# 09-I225-2.net
KiCad netlist of a schematic drawn in Altium Designer
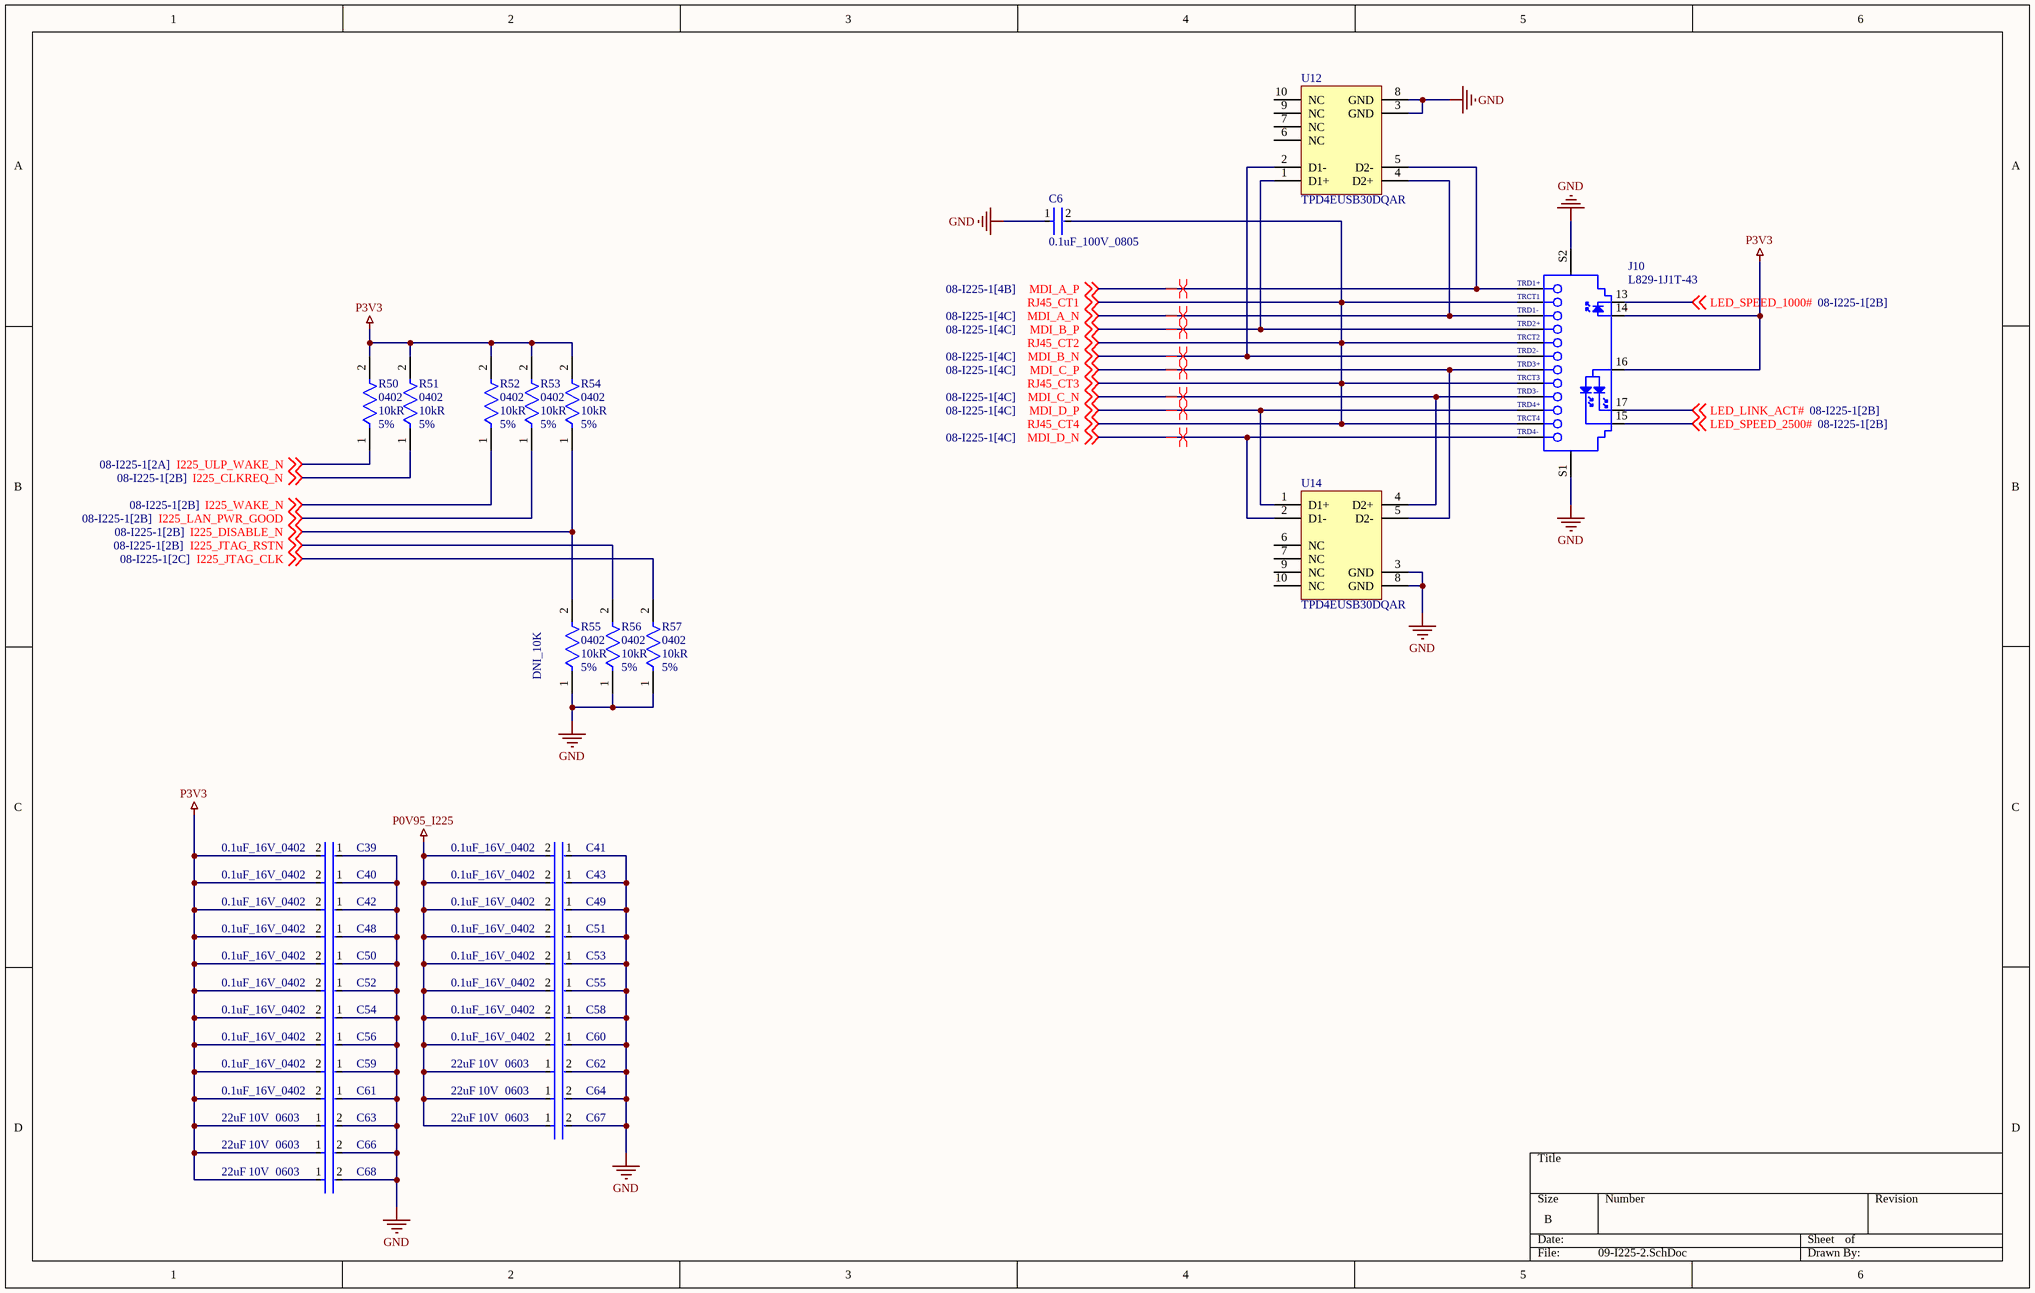
[diagram p0: 09-I225-2.SchDoc]

(export (version "E")
  (design (tool "Eeschema 10.0.6"))
  (components
    (comp (ref "C6")
      (value "0.1uF_100V_0805")
      (footprint "FP-0805-L_2_0_0_1-W_1_25-MFG")
      (description "Multilayer Ceramic Capacitor 0.1 uF 100V X7R 20% SMD 0805 T/R")
      (fields (field (name "TOLERANCE") "20%"))
      (libsource (lib "Altium Content Vault") (part "b4654b650e69147ec39a6b967a45e02"))
    )
    (comp (ref "C39")
      (value "0.1uF_16V_0402")
      (footprint "FP-GRM15-MFG")
      (description "CAP CER 0.1UF 16V X7R 0402")
      (fields (field (name "MANUFACTURER PART NUMBER") "GRM155R71C104KA88D") (field (name "TOLERANCE") "10%"))
      (libsource (lib "Altium Content Vault") (part "236180d848d6139a670b325ea6854c9"))
    )
    (comp (ref "C40")
      (value "0.1uF_16V_0402")
      (footprint "FP-GRM15-MFG")
      (description "CAP CER 0.1UF 16V X7R 0402")
      (fields (field (name "MANUFACTURER PART NUMBER") "GRM155R71C104KA88D") (field (name "TOLERANCE") "10%"))
      (libsource (lib "Altium Content Vault") (part "236180d848d6139a670b325ea6854c9"))
    )
    (comp (ref "C41")
      (value "0.1uF_16V_0402")
      (footprint "FP-GRM15-MFG")
      (description "CAP CER 0.1UF 16V X7R 0402")
      (fields (field (name "MANUFACTURER PART NUMBER") "GRM155R71C104KA88D") (field (name "TOLERANCE") "10%"))
      (libsource (lib "Altium Content Vault") (part "236180d848d6139a670b325ea6854c9"))
    )
    (comp (ref "C42")
      (value "0.1uF_16V_0402")
      (footprint "FP-GRM15-MFG")
      (description "CAP CER 0.1UF 16V X7R 0402")
      (fields (field (name "MANUFACTURER PART NUMBER") "GRM155R71C104KA88D") (field (name "TOLERANCE") "10%"))
      (libsource (lib "Altium Content Vault") (part "236180d848d6139a670b325ea6854c9"))
    )
    (comp (ref "C43")
      (value "0.1uF_16V_0402")
      (footprint "FP-GRM15-MFG")
      (description "CAP CER 0.1UF 16V X7R 0402")
      (fields (field (name "MANUFACTURER PART NUMBER") "GRM155R71C104KA88D") (field (name "TOLERANCE") "10%"))
      (libsource (lib "Altium Content Vault") (part "236180d848d6139a670b325ea6854c9"))
    )
    (comp (ref "C48")
      (value "0.1uF_16V_0402")
      (footprint "FP-GRM15-MFG")
      (description "CAP CER 0.1UF 16V X7R 0402")
      (fields (field (name "MANUFACTURER PART NUMBER") "GRM155R71C104KA88D") (field (name "TOLERANCE") "10%"))
      (libsource (lib "Altium Content Vault") (part "236180d848d6139a670b325ea6854c9"))
    )
    (comp (ref "C49")
      (value "0.1uF_16V_0402")
      (footprint "FP-GRM15-MFG")
      (description "CAP CER 0.1UF 16V X7R 0402")
      (fields (field (name "MANUFACTURER PART NUMBER") "GRM155R71C104KA88D") (field (name "TOLERANCE") "10%"))
      (libsource (lib "Altium Content Vault") (part "236180d848d6139a670b325ea6854c9"))
    )
    (comp (ref "C50")
      (value "0.1uF_16V_0402")
      (footprint "FP-GRM15-MFG")
      (description "CAP CER 0.1UF 16V X7R 0402")
      (fields (field (name "MANUFACTURER PART NUMBER") "GRM155R71C104KA88D") (field (name "TOLERANCE") "10%"))
      (libsource (lib "Altium Content Vault") (part "236180d848d6139a670b325ea6854c9"))
    )
    (comp (ref "C51")
      (value "0.1uF_16V_0402")
      (footprint "FP-GRM15-MFG")
      (description "CAP CER 0.1UF 16V X7R 0402")
      (fields (field (name "MANUFACTURER PART NUMBER") "GRM155R71C104KA88D") (field (name "TOLERANCE") "10%"))
      (libsource (lib "Altium Content Vault") (part "236180d848d6139a670b325ea6854c9"))
    )
    (comp (ref "C52")
      (value "0.1uF_16V_0402")
      (footprint "FP-GRM15-MFG")
      (description "CAP CER 0.1UF 16V X7R 0402")
      (fields (field (name "MANUFACTURER PART NUMBER") "GRM155R71C104KA88D") (field (name "TOLERANCE") "10%"))
      (libsource (lib "Altium Content Vault") (part "236180d848d6139a670b325ea6854c9"))
    )
    (comp (ref "C53")
      (value "0.1uF_16V_0402")
      (footprint "FP-GRM15-MFG")
      (description "CAP CER 0.1UF 16V X7R 0402")
      (fields (field (name "MANUFACTURER PART NUMBER") "GRM155R71C104KA88D") (field (name "TOLERANCE") "10%"))
      (libsource (lib "Altium Content Vault") (part "236180d848d6139a670b325ea6854c9"))
    )
    (comp (ref "C54")
      (value "0.1uF_16V_0402")
      (footprint "FP-GRM15-MFG")
      (description "CAP CER 0.1UF 16V X7R 0402")
      (fields (field (name "MANUFACTURER PART NUMBER") "GRM155R71C104KA88D") (field (name "TOLERANCE") "10%"))
      (libsource (lib "Altium Content Vault") (part "236180d848d6139a670b325ea6854c9"))
    )
    (comp (ref "C55")
      (value "0.1uF_16V_0402")
      (footprint "FP-GRM15-MFG")
      (description "CAP CER 0.1UF 16V X7R 0402")
      (fields (field (name "MANUFACTURER PART NUMBER") "GRM155R71C104KA88D") (field (name "TOLERANCE") "10%"))
      (libsource (lib "Altium Content Vault") (part "236180d848d6139a670b325ea6854c9"))
    )
    (comp (ref "C56")
      (value "0.1uF_16V_0402")
      (footprint "FP-GRM15-MFG")
      (description "CAP CER 0.1UF 16V X7R 0402")
      (fields (field (name "MANUFACTURER PART NUMBER") "GRM155R71C104KA88D") (field (name "TOLERANCE") "10%"))
      (libsource (lib "Altium Content Vault") (part "236180d848d6139a670b325ea6854c9"))
    )
    (comp (ref "C58")
      (value "0.1uF_16V_0402")
      (footprint "FP-GRM15-MFG")
      (description "CAP CER 0.1UF 16V X7R 0402")
      (fields (field (name "MANUFACTURER PART NUMBER") "GRM155R71C104KA88D") (field (name "TOLERANCE") "10%"))
      (libsource (lib "Altium Content Vault") (part "236180d848d6139a670b325ea6854c9"))
    )
    (comp (ref "C59")
      (value "0.1uF_16V_0402")
      (footprint "FP-GRM15-MFG")
      (description "CAP CER 0.1UF 16V X7R 0402")
      (fields (field (name "MANUFACTURER PART NUMBER") "GRM155R71C104KA88D") (field (name "TOLERANCE") "10%"))
      (libsource (lib "Altium Content Vault") (part "236180d848d6139a670b325ea6854c9"))
    )
    (comp (ref "C60")
      (value "0.1uF_16V_0402")
      (footprint "FP-GRM15-MFG")
      (description "CAP CER 0.1UF 16V X7R 0402")
      (fields (field (name "MANUFACTURER PART NUMBER") "GRM155R71C104KA88D") (field (name "TOLERANCE") "10%"))
      (libsource (lib "Altium Content Vault") (part "236180d848d6139a670b325ea6854c9"))
    )
    (comp (ref "C61")
      (value "0.1uF_16V_0402")
      (footprint "FP-GRM15-MFG")
      (description "CAP CER 0.1UF 16V X7R 0402")
      (fields (field (name "MANUFACTURER PART NUMBER") "GRM155R71C104KA88D") (field (name "TOLERANCE") "10%"))
      (libsource (lib "Altium Content Vault") (part "236180d848d6139a670b325ea6854c9"))
    )
    (comp (ref "C62")
      (value "GRM188R61A226ME15D")
      (footprint "FP-GRM188-0_2-IPC_C")
      (description "Chip Multilayer Ceramic Capacitors for General Purpose, 0603, 22uF, X5R, 15%, 20%, 10V")
      (fields
        (field (name "TOLERANCE") "20%")
        (field (name "CAPACITANCE") "22uF")
        (field (name "VOLTAGE RATING") "10V")
        (field (name "CASE CODE (IMPERIAL)") "0603")
      )
      (libsource (lib "Altium Content Vault") (part "11868f565c42a9108669ba33697ecf6"))
    )
    (comp (ref "C63")
      (value "GRM188R61A226ME15D")
      (footprint "FP-GRM188-0_2-IPC_C")
      (description "Chip Multilayer Ceramic Capacitors for General Purpose, 0603, 22uF, X5R, 15%, 20%, 10V")
      (fields
        (field (name "TOLERANCE") "20%")
        (field (name "CAPACITANCE") "22uF")
        (field (name "VOLTAGE RATING") "10V")
        (field (name "CASE CODE (IMPERIAL)") "0603")
      )
      (libsource (lib "Altium Content Vault") (part "11868f565c42a9108669ba33697ecf6"))
    )
    (comp (ref "C64")
      (value "GRM188R61A226ME15D")
      (footprint "FP-GRM188-0_2-IPC_C")
      (description "Chip Multilayer Ceramic Capacitors for General Purpose, 0603, 22uF, X5R, 15%, 20%, 10V")
      (fields
        (field (name "TOLERANCE") "20%")
        (field (name "CAPACITANCE") "22uF")
        (field (name "VOLTAGE RATING") "10V")
        (field (name "CASE CODE (IMPERIAL)") "0603")
      )
      (libsource (lib "Altium Content Vault") (part "11868f565c42a9108669ba33697ecf6"))
    )
    (comp (ref "C66")
      (value "GRM188R61A226ME15D")
      (footprint "FP-GRM188-0_2-IPC_C")
      (description "Chip Multilayer Ceramic Capacitors for General Purpose, 0603, 22uF, X5R, 15%, 20%, 10V")
      (fields
        (field (name "TOLERANCE") "20%")
        (field (name "CAPACITANCE") "22uF")
        (field (name "VOLTAGE RATING") "10V")
        (field (name "CASE CODE (IMPERIAL)") "0603")
      )
      (libsource (lib "Altium Content Vault") (part "11868f565c42a9108669ba33697ecf6"))
    )
    (comp (ref "C67")
      (value "GRM188R61A226ME15D")
      (footprint "FP-GRM188-0_2-IPC_C")
      (description "Chip Multilayer Ceramic Capacitors for General Purpose, 0603, 22uF, X5R, 15%, 20%, 10V")
      (fields
        (field (name "TOLERANCE") "20%")
        (field (name "CAPACITANCE") "22uF")
        (field (name "VOLTAGE RATING") "10V")
        (field (name "CASE CODE (IMPERIAL)") "0603")
      )
      (libsource (lib "Altium Content Vault") (part "11868f565c42a9108669ba33697ecf6"))
    )
    (comp (ref "C68")
      (value "GRM188R61A226ME15D")
      (footprint "FP-GRM188-0_2-IPC_C")
      (description "Chip Multilayer Ceramic Capacitors for General Purpose, 0603, 22uF, X5R, 15%, 20%, 10V")
      (fields
        (field (name "TOLERANCE") "20%")
        (field (name "CAPACITANCE") "22uF")
        (field (name "VOLTAGE RATING") "10V")
        (field (name "CASE CODE (IMPERIAL)") "0603")
      )
      (libsource (lib "Altium Content Vault") (part "11868f565c42a9108669ba33697ecf6"))
    )
    (comp (ref "J10")
      (value "L829-1J1T-43")
      (footprint "BELS-L829-1J1T-43_V")
      (description "Gigabit MagJack(R) Ultra Low Profile, 10/100/1000 Base-T, 19-Pin THD, RoHS, Tray")
      (libsource (lib "Altium Content Vault") (part "RJ45-17-2SHLD"))
    )
    (comp (ref "R50")
      (value "CRCW040210K0JNED")
      (footprint "FP-CRCW0402-e3-IPC_B")
      (description "RES Thick Film, 10kΩ, 5%, 0.063W, 200ppm/°C, 0402")
      (fields
        (field (name "CASE/PACKAGE") "0402")
        (field (name "RESISTANCE") "10kR")
        (field (name "TOLERANCE") "5%")
      )
      (libsource (lib "Altium Content Vault") (part "1029c3af85768c4190bb7ad29bc67b5"))
    )
    (comp (ref "R51")
      (value "CRCW040210K0JNED")
      (footprint "FP-CRCW0402-e3-IPC_B")
      (description "RES Thick Film, 10kΩ, 5%, 0.063W, 200ppm/°C, 0402")
      (fields
        (field (name "CASE/PACKAGE") "0402")
        (field (name "RESISTANCE") "10kR")
        (field (name "TOLERANCE") "5%")
      )
      (libsource (lib "Altium Content Vault") (part "1029c3af85768c4190bb7ad29bc67b5"))
    )
    (comp (ref "R52")
      (value "CRCW040210K0JNED")
      (footprint "FP-CRCW0402-e3-IPC_B")
      (description "RES Thick Film, 10kΩ, 5%, 0.063W, 200ppm/°C, 0402")
      (fields
        (field (name "CASE/PACKAGE") "0402")
        (field (name "RESISTANCE") "10kR")
        (field (name "TOLERANCE") "5%")
      )
      (libsource (lib "Altium Content Vault") (part "1029c3af85768c4190bb7ad29bc67b5"))
    )
    (comp (ref "R53")
      (value "CRCW040210K0JNED")
      (footprint "FP-CRCW0402-e3-IPC_B")
      (description "RES Thick Film, 10kΩ, 5%, 0.063W, 200ppm/°C, 0402")
      (fields
        (field (name "CASE/PACKAGE") "0402")
        (field (name "RESISTANCE") "10kR")
        (field (name "TOLERANCE") "5%")
      )
      (libsource (lib "Altium Content Vault") (part "1029c3af85768c4190bb7ad29bc67b5"))
    )
    (comp (ref "R54")
      (value "CRCW040210K0JNED")
      (footprint "FP-CRCW0402-e3-IPC_B")
      (description "RES Thick Film, 10kΩ, 5%, 0.063W, 200ppm/°C, 0402")
      (fields
        (field (name "CASE/PACKAGE") "0402")
        (field (name "RESISTANCE") "10kR")
        (field (name "TOLERANCE") "5%")
      )
      (libsource (lib "Altium Content Vault") (part "1029c3af85768c4190bb7ad29bc67b5"))
    )
    (comp (ref "R55")
      (value "DNI_10K")
      (footprint "FP-CRCW0402-e3-IPC_B")
      (description "RES Thick Film, 10kΩ, 5%, 0.063W, 200ppm/°C, 0402")
      (fields
        (field (name "CASE/PACKAGE") "0402")
        (field (name "RESISTANCE") "10kR")
        (field (name "TOLERANCE") "5%")
      )
      (libsource (lib "Altium Content Vault") (part "1029c3af85768c4190bb7ad29bc67b5"))
    )
    (comp (ref "R56")
      (value "CRCW040210K0JNED")
      (footprint "FP-CRCW0402-e3-IPC_B")
      (description "RES Thick Film, 10kΩ, 5%, 0.063W, 200ppm/°C, 0402")
      (fields
        (field (name "CASE/PACKAGE") "0402")
        (field (name "RESISTANCE") "10kR")
        (field (name "TOLERANCE") "5%")
      )
      (libsource (lib "Altium Content Vault") (part "1029c3af85768c4190bb7ad29bc67b5"))
    )
    (comp (ref "R57")
      (value "CRCW040210K0JNED")
      (footprint "FP-CRCW0402-e3-IPC_B")
      (description "RES Thick Film, 10kΩ, 5%, 0.063W, 200ppm/°C, 0402")
      (fields
        (field (name "CASE/PACKAGE") "0402")
        (field (name "RESISTANCE") "10kR")
        (field (name "TOLERANCE") "5%")
      )
      (libsource (lib "Altium Content Vault") (part "1029c3af85768c4190bb7ad29bc67b5"))
    )
    (comp (ref "U12")
      (value "TPD4EUSB30DQAR")
      (footprint "DQA0010A_V")
      (fields (field (name "MANUFACTURER") "Texas Instruments"))
      (libsource (lib "Altium Content Vault") (part "TI-TPD4EUSB30-SON_DQA-10"))
    )
    (comp (ref "U14")
      (value "TPD4EUSB30DQAR")
      (footprint "DQA0010A_V")
      (fields (field (name "MANUFACTURER") "Texas Instruments"))
      (libsource (lib "") (part "TI-TPD4EUSB30-SON_DQA-10_1"))
    )
  )
  (nets
    (net (code "1") (name "GND") (class "Default")
      (node (ref "C39") (pin "1") (pinfunction "1_1") (pintype "passive"))
      (node (ref "C40") (pin "1") (pinfunction "1_1") (pintype "passive"))
      (node (ref "C41") (pin "1") (pinfunction "1_1") (pintype "passive"))
      (node (ref "C42") (pin "1") (pinfunction "1_1") (pintype "passive"))
      (node (ref "C43") (pin "1") (pinfunction "1_1") (pintype "passive"))
      (node (ref "C48") (pin "1") (pinfunction "1_1") (pintype "passive"))
      (node (ref "C49") (pin "1") (pinfunction "1_1") (pintype "passive"))
      (node (ref "C50") (pin "1") (pinfunction "1_1") (pintype "passive"))
      (node (ref "C51") (pin "1") (pinfunction "1_1") (pintype "passive"))
      (node (ref "C52") (pin "1") (pinfunction "1_1") (pintype "passive"))
      (node (ref "C53") (pin "1") (pinfunction "1_1") (pintype "passive"))
      (node (ref "C54") (pin "1") (pinfunction "1_1") (pintype "passive"))
      (node (ref "C55") (pin "1") (pinfunction "1_1") (pintype "passive"))
      (node (ref "C56") (pin "1") (pinfunction "1_1") (pintype "passive"))
      (node (ref "C58") (pin "1") (pinfunction "1_1") (pintype "passive"))
      (node (ref "C59") (pin "1") (pinfunction "1_1") (pintype "passive"))
      (node (ref "C6") (pin "1") (pinfunction "1_1") (pintype "passive"))
      (node (ref "C60") (pin "1") (pinfunction "1_1") (pintype "passive"))
      (node (ref "C61") (pin "1") (pinfunction "1_1") (pintype "passive"))
      (node (ref "C62") (pin "2") (pinfunction "2_2") (pintype "passive"))
      (node (ref "C63") (pin "2") (pinfunction "2_2") (pintype "passive"))
      (node (ref "C64") (pin "2") (pinfunction "2_2") (pintype "passive"))
      (node (ref "C66") (pin "2") (pinfunction "2_2") (pintype "passive"))
      (node (ref "C67") (pin "2") (pinfunction "2_2") (pintype "passive"))
      (node (ref "C68") (pin "2") (pinfunction "2_2") (pintype "passive"))
      (node (ref "J10") (pin "S1") (pinfunction "S1_S1") (pintype "passive"))
      (node (ref "J10") (pin "S2") (pinfunction "S2_S2") (pintype "passive"))
      (node (ref "R55") (pin "1") (pinfunction "1_1") (pintype "passive"))
      (node (ref "R56") (pin "1") (pinfunction "1_1") (pintype "passive"))
      (node (ref "R57") (pin "1") (pinfunction "1_1") (pintype "passive"))
      (node (ref "U12") (pin "3") (pinfunction "GND_3") (pintype "power_in"))
      (node (ref "U12") (pin "8") (pinfunction "GND_8") (pintype "power_in"))
      (node (ref "U14") (pin "3") (pinfunction "GND_3") (pintype "power_in"))
      (node (ref "U14") (pin "8") (pinfunction "GND_8") (pintype "power_in"))
    )
    (net (code "2") (name "I225_CLKREQ_N") (class "Default")
      (node (ref "R51") (pin "1") (pinfunction "1_1") (pintype "passive"))
    )
    (net (code "3") (name "I225_DISABLE_N") (class "Default")
      (node (ref "R54") (pin "1") (pinfunction "1_1") (pintype "passive"))
      (node (ref "R55") (pin "2") (pinfunction "2_2") (pintype "passive"))
    )
    (net (code "4") (name "I225_JTAG_CLK") (class "Default")
      (node (ref "R57") (pin "2") (pinfunction "2_2") (pintype "passive"))
    )
    (net (code "5") (name "I225_JTAG_RSTN") (class "Default")
      (node (ref "R56") (pin "2") (pinfunction "2_2") (pintype "passive"))
    )
    (net (code "6") (name "I225_LAN_PWR_GOOD") (class "Default")
      (node (ref "R53") (pin "1") (pinfunction "1_1") (pintype "passive"))
    )
    (net (code "7") (name "I225_ULP_WAKE_N") (class "Default")
      (node (ref "R50") (pin "1") (pinfunction "1_1") (pintype "passive"))
    )
    (net (code "8") (name "I225_WAKE_N") (class "Default")
      (node (ref "R52") (pin "1") (pinfunction "1_1") (pintype "passive"))
    )
    (net (code "9") (name "LED_LINK_ACT#") (class "Default")
      (node (ref "J10") (pin "17") (pinfunction "17_17") (pintype "passive"))
    )
    (net (code "10") (name "LED_SPEED_1000#") (class "Default")
      (node (ref "J10") (pin "13") (pinfunction "13_13") (pintype "passive"))
    )
    (net (code "11") (name "LED_SPEED_2500#") (class "Default")
      (node (ref "J10") (pin "15") (pinfunction "15_15") (pintype "passive"))
    )
    (net (code "12") (name "MDI_A_N") (class "Default")
      (node (ref "J10") (pin "3") (pinfunction "TRD1-_3") (pintype "passive"))
      (node (ref "U12") (pin "4") (pinfunction "D2+_4") (pintype "passive"))
    )
    (net (code "13") (name "MDI_A_P") (class "Default")
      (node (ref "J10") (pin "1") (pinfunction "TRD1+_1") (pintype "passive"))
      (node (ref "U12") (pin "5") (pinfunction "D2-_5") (pintype "passive"))
    )
    (net (code "14") (name "MDI_B_N") (class "Default")
      (node (ref "J10") (pin "6") (pinfunction "TRD2-_6") (pintype "passive"))
      (node (ref "U12") (pin "2") (pinfunction "D1-_2") (pintype "passive"))
    )
    (net (code "15") (name "MDI_B_P") (class "Default")
      (node (ref "J10") (pin "4") (pinfunction "TRD2+_4") (pintype "passive"))
      (node (ref "U12") (pin "1") (pinfunction "D1+_1") (pintype "passive"))
    )
    (net (code "16") (name "MDI_C_N") (class "Default")
      (node (ref "J10") (pin "9") (pinfunction "TRD3-_9") (pintype "passive"))
      (node (ref "U14") (pin "4") (pinfunction "D2+_4") (pintype "passive"))
    )
    (net (code "17") (name "MDI_C_P") (class "Default")
      (node (ref "J10") (pin "7") (pinfunction "TRD3+_7") (pintype "passive"))
      (node (ref "U14") (pin "5") (pinfunction "D2-_5") (pintype "passive"))
    )
    (net (code "18") (name "MDI_D_N") (class "Default")
      (node (ref "J10") (pin "12") (pinfunction "TRD4-_12") (pintype "passive"))
      (node (ref "U14") (pin "2") (pinfunction "D1-_2") (pintype "passive"))
    )
    (net (code "19") (name "MDI_D_P") (class "Default")
      (node (ref "J10") (pin "10") (pinfunction "TRD4+_10") (pintype "passive"))
      (node (ref "U14") (pin "1") (pinfunction "D1+_1") (pintype "passive"))
    )
    (net (code "20") (name "P0V95_I225") (class "Default")
      (node (ref "C41") (pin "2") (pinfunction "2_2") (pintype "passive"))
      (node (ref "C43") (pin "2") (pinfunction "2_2") (pintype "passive"))
      (node (ref "C49") (pin "2") (pinfunction "2_2") (pintype "passive"))
      (node (ref "C51") (pin "2") (pinfunction "2_2") (pintype "passive"))
      (node (ref "C53") (pin "2") (pinfunction "2_2") (pintype "passive"))
      (node (ref "C55") (pin "2") (pinfunction "2_2") (pintype "passive"))
      (node (ref "C58") (pin "2") (pinfunction "2_2") (pintype "passive"))
      (node (ref "C60") (pin "2") (pinfunction "2_2") (pintype "passive"))
      (node (ref "C62") (pin "1") (pinfunction "1_1") (pintype "passive"))
      (node (ref "C64") (pin "1") (pinfunction "1_1") (pintype "passive"))
      (node (ref "C67") (pin "1") (pinfunction "1_1") (pintype "passive"))
    )
    (net (code "21") (name "P3V3") (class "Default")
      (node (ref "C39") (pin "2") (pinfunction "2_2") (pintype "passive"))
      (node (ref "C40") (pin "2") (pinfunction "2_2") (pintype "passive"))
      (node (ref "C42") (pin "2") (pinfunction "2_2") (pintype "passive"))
      (node (ref "C48") (pin "2") (pinfunction "2_2") (pintype "passive"))
      (node (ref "C50") (pin "2") (pinfunction "2_2") (pintype "passive"))
      (node (ref "C52") (pin "2") (pinfunction "2_2") (pintype "passive"))
      (node (ref "C54") (pin "2") (pinfunction "2_2") (pintype "passive"))
      (node (ref "C56") (pin "2") (pinfunction "2_2") (pintype "passive"))
      (node (ref "C59") (pin "2") (pinfunction "2_2") (pintype "passive"))
      (node (ref "C61") (pin "2") (pinfunction "2_2") (pintype "passive"))
      (node (ref "C63") (pin "1") (pinfunction "1_1") (pintype "passive"))
      (node (ref "C66") (pin "1") (pinfunction "1_1") (pintype "passive"))
      (node (ref "C68") (pin "1") (pinfunction "1_1") (pintype "passive"))
      (node (ref "J10") (pin "14") (pinfunction "14_14") (pintype "passive"))
      (node (ref "J10") (pin "16") (pinfunction "16_16") (pintype "passive"))
      (node (ref "R50") (pin "2") (pinfunction "2_2") (pintype "passive"))
      (node (ref "R51") (pin "2") (pinfunction "2_2") (pintype "passive"))
      (node (ref "R52") (pin "2") (pinfunction "2_2") (pintype "passive"))
      (node (ref "R53") (pin "2") (pinfunction "2_2") (pintype "passive"))
      (node (ref "R54") (pin "2") (pinfunction "2_2") (pintype "passive"))
    )
    (net (code "22") (name "RJ45_CT1") (class "Default")
      (node (ref "C6") (pin "2") (pinfunction "2_2") (pintype "passive"))
      (node (ref "J10") (pin "11") (pinfunction "TRCT4_11") (pintype "passive"))
      (node (ref "J10") (pin "2") (pinfunction "TRCT1_2") (pintype "passive"))
      (node (ref "J10") (pin "5") (pinfunction "TRCT2_5") (pintype "passive"))
      (node (ref "J10") (pin "8") (pinfunction "TRCT3_8") (pintype "passive"))
    )
    (net (code "23") (name "unconnected-(U12-NC-Pad6)") (class "Default")
      (node (ref "U12") (pin "6") (pinfunction "NC_6") (pintype "passive"))
    )
    (net (code "24") (name "unconnected-(U12-NC-Pad7)") (class "Default")
      (node (ref "U12") (pin "7") (pinfunction "NC_7") (pintype "passive"))
    )
    (net (code "25") (name "unconnected-(U12-NC-Pad9)") (class "Default")
      (node (ref "U12") (pin "9") (pinfunction "NC_9") (pintype "passive"))
    )
    (net (code "26") (name "unconnected-(U12-NC-Pad10)") (class "Default")
      (node (ref "U12") (pin "10") (pinfunction "NC_10") (pintype "passive"))
    )
    (net (code "27") (name "unconnected-(U14-NC-Pad6)") (class "Default")
      (node (ref "U14") (pin "6") (pinfunction "NC_6") (pintype "passive"))
    )
    (net (code "28") (name "unconnected-(U14-NC-Pad7)") (class "Default")
      (node (ref "U14") (pin "7") (pinfunction "NC_7") (pintype "passive"))
    )
    (net (code "29") (name "unconnected-(U14-NC-Pad9)") (class "Default")
      (node (ref "U14") (pin "9") (pinfunction "NC_9") (pintype "passive"))
    )
    (net (code "30") (name "unconnected-(U14-NC-Pad10)") (class "Default")
      (node (ref "U14") (pin "10") (pinfunction "NC_10") (pintype "passive"))
    )
  )
)
